# ablogger_doublewing.net
KiCad netlist of a schematic drawn in EAGLE
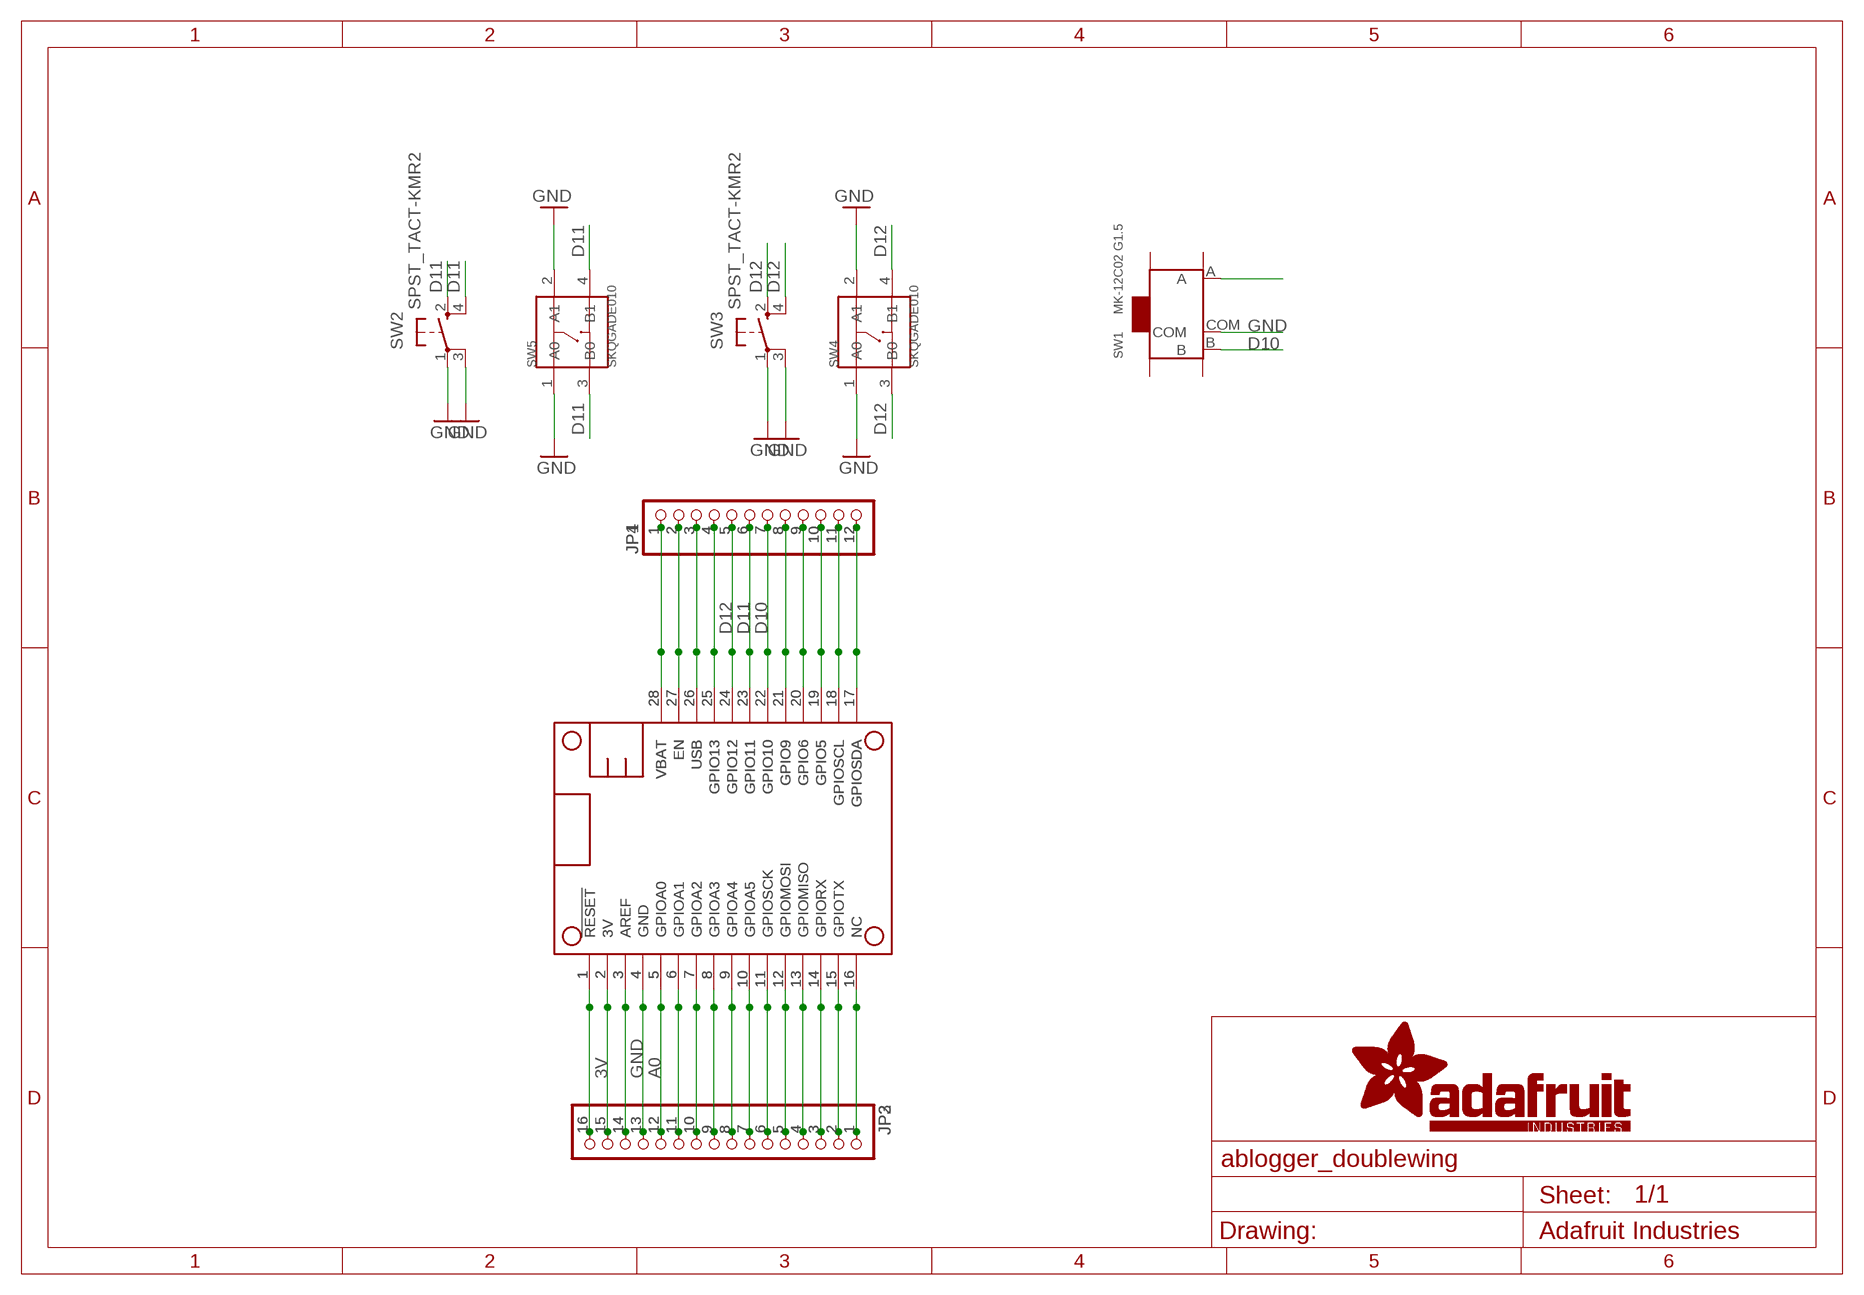
[diagram p0: schematic, sheet 1]

(export (version "E")
  (design (tool "Eeschema 10.0.6"))
  (components
    (comp (ref "JP1")
      (value "HEADER-1X1276MIL")
      (footprint "eagle-import:1X12_ROUND_76MIL")
      (libsource (lib "eagle-import") (part "HEADER-1X1276MIL"))
    )
    (comp (ref "JP2")
      (value "HEADER-1X16_76MIL")
      (footprint "eagle-import:1X16_ROUND_76MIL")
      (libsource (lib "eagle-import") (part "HEADER-1X16_76MIL"))
    )
    (comp (ref "JP3")
      (value "HEADER-1X16_76MIL")
      (footprint "eagle-import:1X16_ROUND_76MIL")
      (libsource (lib "eagle-import") (part "HEADER-1X16_76MIL"))
    )
    (comp (ref "JP4")
      (value "HEADER-1X1276MIL")
      (footprint "eagle-import:1X12_ROUND_76MIL")
      (libsource (lib "eagle-import") (part "HEADER-1X1276MIL"))
    )
    (comp (ref "MS1")
      (value "FEATHERWING_NODIM")
      (footprint "eagle-import:FEATHERWING_DIM")
      (libsource (lib "eagle-import") (part "FEATHERWING_NODIM"))
    )
    (comp (ref "MS2")
      (value "FEATHERWING_NODIM")
      (footprint "eagle-import:FEATHERWING_DIM")
      (libsource (lib "eagle-import") (part "FEATHERWING_NODIM"))
    )
    (comp (ref "SW1")
      (value "MK-12C02 G1.5")
      (footprint "eagle-import:SW7-SMD-L6.7X2.7X3.2MM")
      (libsource (lib "eagle-import") (part "SMD-TOGGLE-SWITCH-ON-ON(3+4P-6.7X2.7MM)"))
    )
    (comp (ref "SW2")
      (value "SPST_TACT-KMR2")
      (footprint "eagle-import:KMR2")
      (libsource (lib "eagle-import") (part "SPST_TACT-KMR2"))
    )
    (comp (ref "SW3")
      (value "SPST_TACT-KMR2")
      (footprint "eagle-import:KMR2")
      (libsource (lib "eagle-import") (part "SPST_TACT-KMR2"))
    )
    (comp (ref "SW4")
      (value "SKQGADE010")
      (footprint "eagle-import:SW4-SMD-5.2X5.2X1.5MM")
      (libsource (lib "eagle-import") (part "SMD-BUTTON(4P-5.2X5.2X1.5MM-SKQGADE010)-SKQGADE010"))
    )
    (comp (ref "SW5")
      (value "SKQGADE010")
      (footprint "eagle-import:SW4-SMD-5.2X5.2X1.5MM")
      (libsource (lib "eagle-import") (part "SMD-BUTTON(4P-5.2X5.2X1.5MM-SKQGADE010)-SKQGADE010"))
    )
  )
  (nets
    (net (code "1") (name "/3V") (class "Default")
      (node (ref "JP2") (pin "15") (pinfunction "15_15") (pintype "passive"))
      (node (ref "JP3") (pin "15") (pinfunction "15_15") (pintype "passive"))
      (node (ref "MS1") (pin "2") (pinfunction "3V_2") (pintype "power_in"))
      (node (ref "MS2") (pin "2") (pinfunction "3V_2") (pintype "power_in"))
    )
    (net (code "2") (name "/A0") (class "Default")
      (node (ref "JP2") (pin "12") (pinfunction "12_12") (pintype "passive"))
      (node (ref "JP3") (pin "12") (pinfunction "12_12") (pintype "passive"))
      (node (ref "MS1") (pin "5") (pinfunction "GPIOA0_5") (pintype "bidirectional"))
      (node (ref "MS2") (pin "5") (pinfunction "GPIOA0_5") (pintype "bidirectional"))
    )
    (net (code "3") (name "/D10") (class "Default")
      (node (ref "JP1") (pin "7") (pinfunction "7_7") (pintype "passive"))
      (node (ref "JP4") (pin "7") (pinfunction "7_7") (pintype "passive"))
      (node (ref "MS1") (pin "22") (pinfunction "GPIO10_22") (pintype "bidirectional"))
      (node (ref "MS2") (pin "22") (pinfunction "GPIO10_22") (pintype "bidirectional"))
      (node (ref "SW1") (pin "B") (pinfunction "B_B") (pintype "bidirectional"))
    )
    (net (code "4") (name "/D11") (class "Default")
      (node (ref "JP1") (pin "6") (pinfunction "6_6") (pintype "passive"))
      (node (ref "JP4") (pin "6") (pinfunction "6_6") (pintype "passive"))
      (node (ref "MS1") (pin "23") (pinfunction "GPIO11_23") (pintype "bidirectional"))
      (node (ref "MS2") (pin "23") (pinfunction "GPIO11_23") (pintype "bidirectional"))
      (node (ref "SW2") (pin "2") (pinfunction "S_2") (pintype "passive"))
      (node (ref "SW2") (pin "4") (pinfunction "S1_4") (pintype "passive"))
      (node (ref "SW5") (pin "3") (pinfunction "B0_3") (pintype "bidirectional"))
      (node (ref "SW5") (pin "4") (pinfunction "B1_4") (pintype "bidirectional"))
    )
    (net (code "5") (name "/D12") (class "Default")
      (node (ref "JP1") (pin "5") (pinfunction "5_5") (pintype "passive"))
      (node (ref "JP4") (pin "5") (pinfunction "5_5") (pintype "passive"))
      (node (ref "MS1") (pin "24") (pinfunction "GPIO12_24") (pintype "bidirectional"))
      (node (ref "MS2") (pin "24") (pinfunction "GPIO12_24") (pintype "bidirectional"))
      (node (ref "SW3") (pin "2") (pinfunction "S_2") (pintype "passive"))
      (node (ref "SW3") (pin "4") (pinfunction "S1_4") (pintype "passive"))
      (node (ref "SW4") (pin "3") (pinfunction "B0_3") (pintype "bidirectional"))
      (node (ref "SW4") (pin "4") (pinfunction "B1_4") (pintype "bidirectional"))
    )
    (net (code "6") (name "GND") (class "Default")
      (node (ref "JP2") (pin "13") (pinfunction "13_13") (pintype "passive"))
      (node (ref "JP3") (pin "13") (pinfunction "13_13") (pintype "passive"))
      (node (ref "MS1") (pin "4") (pinfunction "GND_4") (pintype "power_in"))
      (node (ref "MS2") (pin "4") (pinfunction "GND_4") (pintype "power_in"))
      (node (ref "SW1") (pin "COM") (pinfunction "COM_COM") (pintype "bidirectional"))
      (node (ref "SW2") (pin "1") (pinfunction "P_1") (pintype "passive"))
      (node (ref "SW2") (pin "3") (pinfunction "P1_3") (pintype "passive"))
      (node (ref "SW3") (pin "1") (pinfunction "P_1") (pintype "passive"))
      (node (ref "SW3") (pin "3") (pinfunction "P1_3") (pintype "passive"))
      (node (ref "SW4") (pin "1") (pinfunction "A0_1") (pintype "bidirectional"))
      (node (ref "SW4") (pin "2") (pinfunction "A1_2") (pintype "bidirectional"))
      (node (ref "SW5") (pin "1") (pinfunction "A0_1") (pintype "bidirectional"))
      (node (ref "SW5") (pin "2") (pinfunction "A1_2") (pintype "bidirectional"))
    )
    (net (code "7") (name "Net-(MS1-AREF)") (class "Default")
      (node (ref "JP2") (pin "14") (pinfunction "14_14") (pintype "passive"))
      (node (ref "JP3") (pin "14") (pinfunction "14_14") (pintype "passive"))
      (node (ref "MS1") (pin "3") (pinfunction "AREF_3") (pintype "passive"))
      (node (ref "MS2") (pin "3") (pinfunction "AREF_3") (pintype "passive"))
    )
    (net (code "8") (name "Net-(MS1-EN)") (class "Default")
      (node (ref "JP1") (pin "2") (pinfunction "2_2") (pintype "passive"))
      (node (ref "JP4") (pin "2") (pinfunction "2_2") (pintype "passive"))
      (node (ref "MS1") (pin "27") (pinfunction "EN_27") (pintype "passive"))
      (node (ref "MS2") (pin "27") (pinfunction "EN_27") (pintype "passive"))
    )
    (net (code "9") (name "Net-(MS1-GPIO5)") (class "Default")
      (node (ref "JP1") (pin "10") (pinfunction "10_10") (pintype "passive"))
      (node (ref "JP4") (pin "10") (pinfunction "10_10") (pintype "passive"))
      (node (ref "MS1") (pin "19") (pinfunction "GPIO5_19") (pintype "bidirectional"))
      (node (ref "MS2") (pin "19") (pinfunction "GPIO5_19") (pintype "bidirectional"))
    )
    (net (code "10") (name "Net-(MS1-GPIO6)") (class "Default")
      (node (ref "JP1") (pin "9") (pinfunction "9_9") (pintype "passive"))
      (node (ref "JP4") (pin "9") (pinfunction "9_9") (pintype "passive"))
      (node (ref "MS1") (pin "20") (pinfunction "GPIO6_20") (pintype "bidirectional"))
      (node (ref "MS2") (pin "20") (pinfunction "GPIO6_20") (pintype "bidirectional"))
    )
    (net (code "11") (name "Net-(MS1-GPIO9)") (class "Default")
      (node (ref "JP1") (pin "8") (pinfunction "8_8") (pintype "passive"))
      (node (ref "JP4") (pin "8") (pinfunction "8_8") (pintype "passive"))
      (node (ref "MS1") (pin "21") (pinfunction "GPIO9_21") (pintype "bidirectional"))
      (node (ref "MS2") (pin "21") (pinfunction "GPIO9_21") (pintype "bidirectional"))
    )
    (net (code "12") (name "Net-(MS1-GPIO13)") (class "Default")
      (node (ref "JP1") (pin "4") (pinfunction "4_4") (pintype "passive"))
      (node (ref "JP4") (pin "4") (pinfunction "4_4") (pintype "passive"))
      (node (ref "MS1") (pin "25") (pinfunction "GPIO13_25") (pintype "bidirectional"))
      (node (ref "MS2") (pin "25") (pinfunction "GPIO13_25") (pintype "bidirectional"))
    )
    (net (code "13") (name "Net-(MS1-GPIOA1)") (class "Default")
      (node (ref "JP2") (pin "11") (pinfunction "11_11") (pintype "passive"))
      (node (ref "JP3") (pin "11") (pinfunction "11_11") (pintype "passive"))
      (node (ref "MS1") (pin "6") (pinfunction "GPIOA1_6") (pintype "bidirectional"))
      (node (ref "MS2") (pin "6") (pinfunction "GPIOA1_6") (pintype "bidirectional"))
    )
    (net (code "14") (name "Net-(MS1-GPIOA2)") (class "Default")
      (node (ref "JP2") (pin "10") (pinfunction "10_10") (pintype "passive"))
      (node (ref "JP3") (pin "10") (pinfunction "10_10") (pintype "passive"))
      (node (ref "MS1") (pin "7") (pinfunction "GPIOA2_7") (pintype "bidirectional"))
      (node (ref "MS2") (pin "7") (pinfunction "GPIOA2_7") (pintype "bidirectional"))
    )
    (net (code "15") (name "Net-(MS1-GPIOA3)") (class "Default")
      (node (ref "JP2") (pin "9") (pinfunction "9_9") (pintype "passive"))
      (node (ref "JP3") (pin "9") (pinfunction "9_9") (pintype "passive"))
      (node (ref "MS1") (pin "8") (pinfunction "GPIOA3_8") (pintype "bidirectional"))
      (node (ref "MS2") (pin "8") (pinfunction "GPIOA3_8") (pintype "bidirectional"))
    )
    (net (code "16") (name "Net-(MS1-GPIOA4)") (class "Default")
      (node (ref "JP2") (pin "8") (pinfunction "8_8") (pintype "passive"))
      (node (ref "JP3") (pin "8") (pinfunction "8_8") (pintype "passive"))
      (node (ref "MS1") (pin "9") (pinfunction "GPIOA4_9") (pintype "bidirectional"))
      (node (ref "MS2") (pin "9") (pinfunction "GPIOA4_9") (pintype "bidirectional"))
    )
    (net (code "17") (name "Net-(MS1-GPIOA5)") (class "Default")
      (node (ref "JP2") (pin "7") (pinfunction "7_7") (pintype "passive"))
      (node (ref "JP3") (pin "7") (pinfunction "7_7") (pintype "passive"))
      (node (ref "MS1") (pin "10") (pinfunction "GPIOA5_10") (pintype "bidirectional"))
      (node (ref "MS2") (pin "10") (pinfunction "GPIOA5_10") (pintype "bidirectional"))
    )
    (net (code "18") (name "Net-(MS1-GPIOMISO)") (class "Default")
      (node (ref "JP2") (pin "4") (pinfunction "4_4") (pintype "passive"))
      (node (ref "JP3") (pin "4") (pinfunction "4_4") (pintype "passive"))
      (node (ref "MS1") (pin "13") (pinfunction "GPIOMISO_13") (pintype "bidirectional"))
      (node (ref "MS2") (pin "13") (pinfunction "GPIOMISO_13") (pintype "bidirectional"))
    )
    (net (code "19") (name "Net-(MS1-GPIOMOSI)") (class "Default")
      (node (ref "JP2") (pin "5") (pinfunction "5_5") (pintype "passive"))
      (node (ref "JP3") (pin "5") (pinfunction "5_5") (pintype "passive"))
      (node (ref "MS1") (pin "12") (pinfunction "GPIOMOSI_12") (pintype "bidirectional"))
      (node (ref "MS2") (pin "12") (pinfunction "GPIOMOSI_12") (pintype "bidirectional"))
    )
    (net (code "20") (name "Net-(MS1-GPIORX)") (class "Default")
      (node (ref "JP2") (pin "3") (pinfunction "3_3") (pintype "passive"))
      (node (ref "JP3") (pin "3") (pinfunction "3_3") (pintype "passive"))
      (node (ref "MS1") (pin "14") (pinfunction "GPIORX_14") (pintype "bidirectional"))
      (node (ref "MS2") (pin "14") (pinfunction "GPIORX_14") (pintype "bidirectional"))
    )
    (net (code "21") (name "Net-(MS1-GPIOSCK)") (class "Default")
      (node (ref "JP2") (pin "6") (pinfunction "6_6") (pintype "passive"))
      (node (ref "JP3") (pin "6") (pinfunction "6_6") (pintype "passive"))
      (node (ref "MS1") (pin "11") (pinfunction "GPIOSCK_11") (pintype "bidirectional"))
      (node (ref "MS2") (pin "11") (pinfunction "GPIOSCK_11") (pintype "bidirectional"))
    )
    (net (code "22") (name "Net-(MS1-GPIOSCL)") (class "Default")
      (node (ref "JP1") (pin "11") (pinfunction "11_11") (pintype "passive"))
      (node (ref "JP4") (pin "11") (pinfunction "11_11") (pintype "passive"))
      (node (ref "MS1") (pin "18") (pinfunction "GPIOSCL_18") (pintype "bidirectional"))
      (node (ref "MS2") (pin "18") (pinfunction "GPIOSCL_18") (pintype "bidirectional"))
    )
    (net (code "23") (name "Net-(MS1-GPIOSDA)") (class "Default")
      (node (ref "JP1") (pin "12") (pinfunction "12_12") (pintype "passive"))
      (node (ref "JP4") (pin "12") (pinfunction "12_12") (pintype "passive"))
      (node (ref "MS1") (pin "17") (pinfunction "GPIOSDA_17") (pintype "bidirectional"))
      (node (ref "MS2") (pin "17") (pinfunction "GPIOSDA_17") (pintype "bidirectional"))
    )
    (net (code "24") (name "Net-(MS1-GPIOTX)") (class "Default")
      (node (ref "JP2") (pin "2") (pinfunction "2_2") (pintype "passive"))
      (node (ref "JP3") (pin "2") (pinfunction "2_2") (pintype "passive"))
      (node (ref "MS1") (pin "15") (pinfunction "GPIOTX_15") (pintype "bidirectional"))
      (node (ref "MS2") (pin "15") (pinfunction "GPIOTX_15") (pintype "bidirectional"))
    )
    (net (code "25") (name "Net-(MS1-NC)") (class "Default")
      (node (ref "JP2") (pin "1") (pinfunction "1_1") (pintype "passive"))
      (node (ref "JP3") (pin "1") (pinfunction "1_1") (pintype "passive"))
      (node (ref "MS1") (pin "16") (pinfunction "NC_16") (pintype "passive"))
      (node (ref "MS2") (pin "16") (pinfunction "NC_16") (pintype "passive"))
    )
    (net (code "26") (name "Net-(MS1-USB)") (class "Default")
      (node (ref "JP1") (pin "3") (pinfunction "3_3") (pintype "passive"))
      (node (ref "JP4") (pin "3") (pinfunction "3_3") (pintype "passive"))
      (node (ref "MS1") (pin "26") (pinfunction "USB_26") (pintype "power_in"))
      (node (ref "MS2") (pin "26") (pinfunction "USB_26") (pintype "power_in"))
    )
    (net (code "27") (name "Net-(MS1-VBAT)") (class "Default")
      (node (ref "JP1") (pin "1") (pinfunction "1_1") (pintype "passive"))
      (node (ref "JP4") (pin "1") (pinfunction "1_1") (pintype "passive"))
      (node (ref "MS1") (pin "28") (pinfunction "VBAT_28") (pintype "power_in"))
      (node (ref "MS2") (pin "28") (pinfunction "VBAT_28") (pintype "power_in"))
    )
    (net (code "28") (name "Net-(MS1-~{RESET})") (class "Default")
      (node (ref "JP2") (pin "16") (pinfunction "16_16") (pintype "passive"))
      (node (ref "JP3") (pin "16") (pinfunction "16_16") (pintype "passive"))
      (node (ref "MS1") (pin "1") (pinfunction "~{RESET}_1") (pintype "input"))
      (node (ref "MS2") (pin "1") (pinfunction "~{RESET}_1") (pintype "input"))
    )
    (net (code "29") (name "unconnected-(SW1-PadA)") (class "Default")
      (node (ref "SW1") (pin "A") (pinfunction "A_A") (pintype "bidirectional"))
    )
    (net (code "30") (name "unconnected-(SW1-PadSS1)") (class "Default")
      (node (ref "SW1") (pin "SS1") (pinfunction "SS1_SS1") (pintype "bidirectional"))
    )
    (net (code "31") (name "unconnected-(SW1-PadSS2)") (class "Default")
      (node (ref "SW1") (pin "SS2") (pinfunction "SS2_SS2") (pintype "bidirectional"))
    )
    (net (code "32") (name "unconnected-(SW1-PadSS3)") (class "Default")
      (node (ref "SW1") (pin "SS3") (pinfunction "SS3_SS3") (pintype "bidirectional"))
    )
    (net (code "33") (name "unconnected-(SW1-PadSS4)") (class "Default")
      (node (ref "SW1") (pin "SS4") (pinfunction "SS4_SS4") (pintype "bidirectional"))
    )
  )
)
